# 5_Cooling_Control.net
KiCad netlist of a schematic drawn in Altium Designer
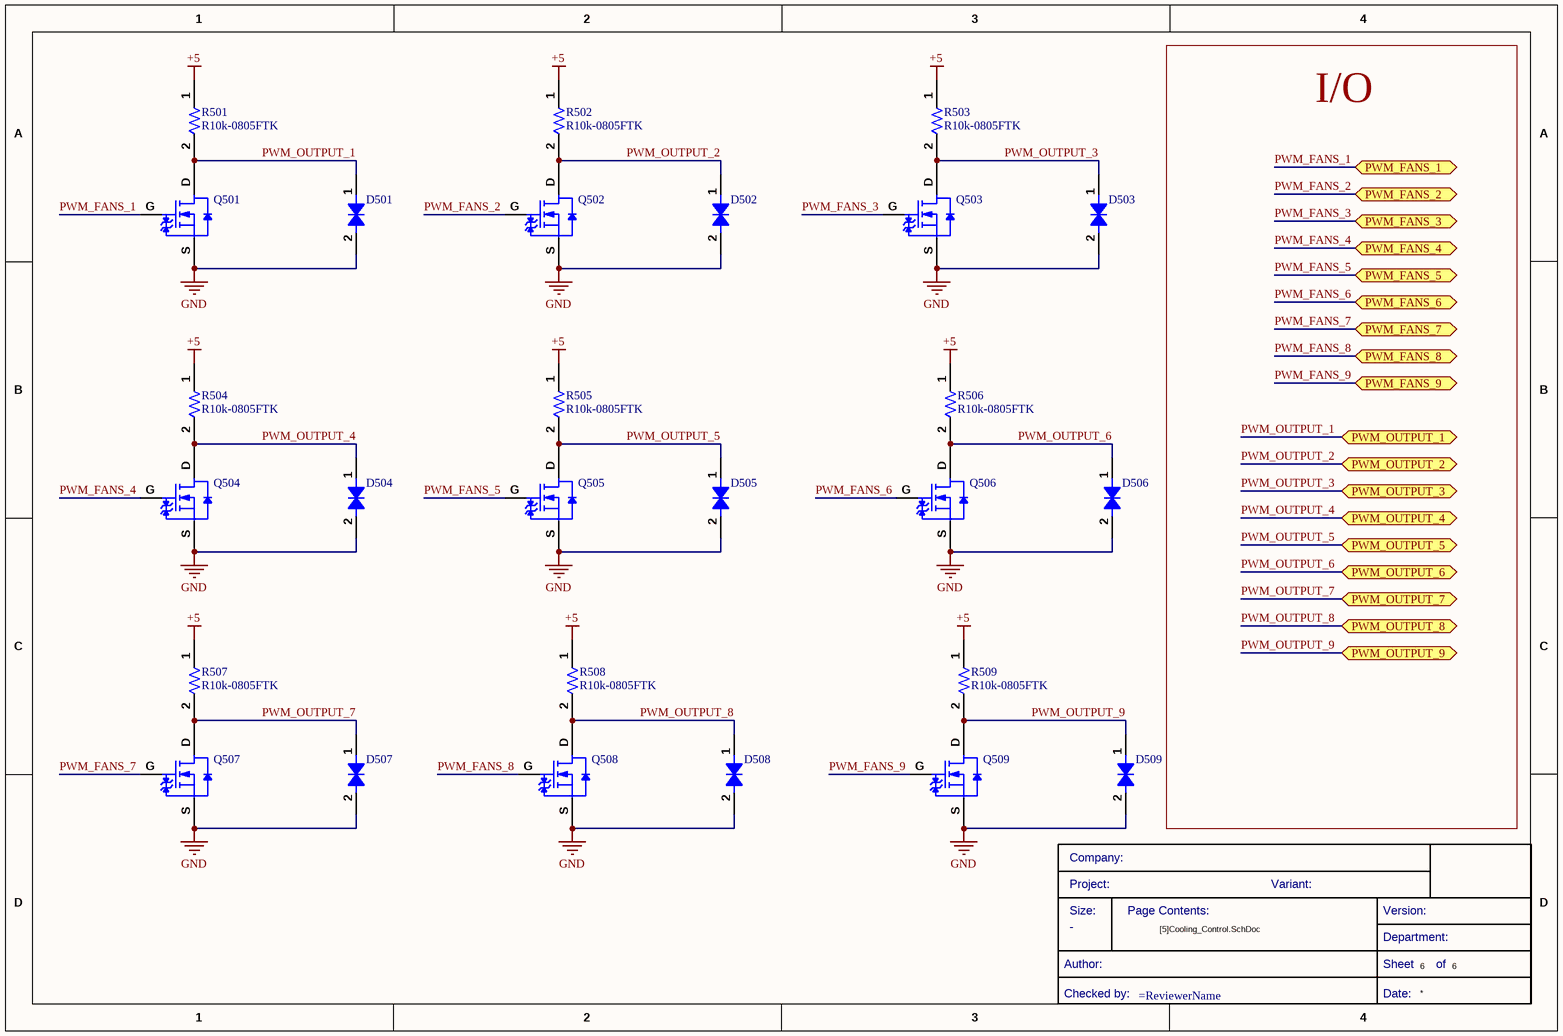
[diagram p0: [5]Cooling_Control.SchDoc]

(export (version "E")
  (design (tool "Eeschema 10.0.6"))
  (components
    (comp (ref "D501")
      (value "DTVS-13V-DO-214AC")
      (footprint "DTVS-DO-214AC")
      (description "Tvs Diode, 400W, 13V, Bidir, DO-214AC")
      (fields
        (field (name "MANUFACTURER PART NUMBER") "824501131")
        (field (name "MANUFACTURER") "Wurth Electronics")
        (field (name ".CREATOR") "DO")
      )
      (libsource (lib "EMEA- E-Tech Racing- I'Escola d'Enginyeria de Barcelona Est") (part "DTVS-BD-30k-SOD323"))
    )
    (comp (ref "D502")
      (value "DTVS-13V-DO-214AC")
      (footprint "DTVS-DO-214AC")
      (description "Tvs Diode, 400W, 13V, Bidir, DO-214AC")
      (fields
        (field (name "MANUFACTURER PART NUMBER") "824501131")
        (field (name "MANUFACTURER") "Wurth Electronics")
        (field (name ".CREATOR") "DO")
      )
      (libsource (lib "EMEA- E-Tech Racing- I'Escola d'Enginyeria de Barcelona Est") (part "DTVS-BD-30k-SOD323"))
    )
    (comp (ref "D503")
      (value "DTVS-13V-DO-214AC")
      (footprint "DTVS-DO-214AC")
      (description "Tvs Diode, 400W, 13V, Bidir, DO-214AC")
      (fields
        (field (name "MANUFACTURER PART NUMBER") "824501131")
        (field (name "MANUFACTURER") "Wurth Electronics")
        (field (name ".CREATOR") "DO")
      )
      (libsource (lib "EMEA- E-Tech Racing- I'Escola d'Enginyeria de Barcelona Est") (part "DTVS-BD-30k-SOD323"))
    )
    (comp (ref "D504")
      (value "DTVS-13V-DO-214AC")
      (footprint "DTVS-DO-214AC")
      (description "Tvs Diode, 400W, 13V, Bidir, DO-214AC")
      (fields
        (field (name "MANUFACTURER PART NUMBER") "824501131")
        (field (name "MANUFACTURER") "Wurth Electronics")
        (field (name ".CREATOR") "DO")
      )
      (libsource (lib "EMEA- E-Tech Racing- I'Escola d'Enginyeria de Barcelona Est") (part "DTVS-BD-30k-SOD323"))
    )
    (comp (ref "D505")
      (value "DTVS-13V-DO-214AC")
      (footprint "DTVS-DO-214AC")
      (description "Tvs Diode, 400W, 13V, Bidir, DO-214AC")
      (fields
        (field (name "MANUFACTURER PART NUMBER") "824501131")
        (field (name "MANUFACTURER") "Wurth Electronics")
        (field (name ".CREATOR") "DO")
      )
      (libsource (lib "EMEA- E-Tech Racing- I'Escola d'Enginyeria de Barcelona Est") (part "DTVS-BD-30k-SOD323"))
    )
    (comp (ref "D506")
      (value "DTVS-13V-DO-214AC")
      (footprint "DTVS-DO-214AC")
      (description "Tvs Diode, 400W, 13V, Bidir, DO-214AC")
      (fields
        (field (name "MANUFACTURER PART NUMBER") "824501131")
        (field (name "MANUFACTURER") "Wurth Electronics")
        (field (name ".CREATOR") "DO")
      )
      (libsource (lib "EMEA- E-Tech Racing- I'Escola d'Enginyeria de Barcelona Est") (part "DTVS-BD-30k-SOD323"))
    )
    (comp (ref "D507")
      (value "DTVS-13V-DO-214AC")
      (footprint "DTVS-DO-214AC")
      (description "Tvs Diode, 400W, 13V, Bidir, DO-214AC")
      (fields
        (field (name "MANUFACTURER PART NUMBER") "824501131")
        (field (name "MANUFACTURER") "Wurth Electronics")
        (field (name ".CREATOR") "DO")
      )
      (libsource (lib "EMEA- E-Tech Racing- I'Escola d'Enginyeria de Barcelona Est") (part "DTVS-BD-30k-SOD323"))
    )
    (comp (ref "D508")
      (value "DTVS-13V-DO-214AC")
      (footprint "DTVS-DO-214AC")
      (description "Tvs Diode, 400W, 13V, Bidir, DO-214AC")
      (fields
        (field (name "MANUFACTURER PART NUMBER") "824501131")
        (field (name "MANUFACTURER") "Wurth Electronics")
        (field (name ".CREATOR") "DO")
      )
      (libsource (lib "EMEA- E-Tech Racing- I'Escola d'Enginyeria de Barcelona Est") (part "DTVS-BD-30k-SOD323"))
    )
    (comp (ref "D509")
      (value "DTVS-13V-DO-214AC")
      (footprint "DTVS-DO-214AC")
      (description "Tvs Diode, 400W, 13V, Bidir, DO-214AC")
      (fields
        (field (name "MANUFACTURER PART NUMBER") "824501131")
        (field (name "MANUFACTURER") "Wurth Electronics")
        (field (name ".CREATOR") "DO")
      )
      (libsource (lib "EMEA- E-Tech Racing- I'Escola d'Enginyeria de Barcelona Est") (part "DTVS-BD-30k-SOD323"))
    )
    (comp (ref "Q501")
      (value "SQ2318CES-T1_GE3")
      (footprint "SOT95P245X110-3N")
      (description "Mosfet, N-channel, 40V, 7A, SOT-23 Rohs Compliant: Yes")
      (libsource (lib "EMEA- E-Tech Racing- I'Escola d'Enginyeria de Barcelona Est") (part "TRT-NCH-3/35-CPH"))
    )
    (comp (ref "Q502")
      (value "SQ2318CES-T1_GE3")
      (footprint "SOT95P245X110-3N")
      (description "Mosfet, N-channel, 40V, 7A, SOT-23 Rohs Compliant: Yes")
      (libsource (lib "EMEA- E-Tech Racing- I'Escola d'Enginyeria de Barcelona Est") (part "TRT-NCH-3/35-CPH"))
    )
    (comp (ref "Q503")
      (value "SQ2318CES-T1_GE3")
      (footprint "SOT95P245X110-3N")
      (description "Mosfet, N-channel, 40V, 7A, SOT-23 Rohs Compliant: Yes")
      (libsource (lib "EMEA- E-Tech Racing- I'Escola d'Enginyeria de Barcelona Est") (part "TRT-NCH-3/35-CPH"))
    )
    (comp (ref "Q504")
      (value "SQ2318CES-T1_GE3")
      (footprint "SOT95P245X110-3N")
      (description "Mosfet, N-channel, 40V, 7A, SOT-23 Rohs Compliant: Yes")
      (libsource (lib "EMEA- E-Tech Racing- I'Escola d'Enginyeria de Barcelona Est") (part "TRT-NCH-3/35-CPH"))
    )
    (comp (ref "Q505")
      (value "SQ2318CES-T1_GE3")
      (footprint "SOT95P245X110-3N")
      (description "Mosfet, N-channel, 40V, 7A, SOT-23 Rohs Compliant: Yes")
      (libsource (lib "EMEA- E-Tech Racing- I'Escola d'Enginyeria de Barcelona Est") (part "TRT-NCH-3/35-CPH"))
    )
    (comp (ref "Q506")
      (value "SQ2318CES-T1_GE3")
      (footprint "SOT95P245X110-3N")
      (description "Mosfet, N-channel, 40V, 7A, SOT-23 Rohs Compliant: Yes")
      (libsource (lib "EMEA- E-Tech Racing- I'Escola d'Enginyeria de Barcelona Est") (part "TRT-NCH-3/35-CPH"))
    )
    (comp (ref "Q507")
      (value "SQ2318CES-T1_GE3")
      (footprint "SOT95P245X110-3N")
      (description "Mosfet, N-channel, 40V, 7A, SOT-23 Rohs Compliant: Yes")
      (libsource (lib "EMEA- E-Tech Racing- I'Escola d'Enginyeria de Barcelona Est") (part "TRT-NCH-3/35-CPH"))
    )
    (comp (ref "Q508")
      (value "SQ2318CES-T1_GE3")
      (footprint "SOT95P245X110-3N")
      (description "Mosfet, N-channel, 40V, 7A, SOT-23 Rohs Compliant: Yes")
      (libsource (lib "EMEA- E-Tech Racing- I'Escola d'Enginyeria de Barcelona Est") (part "TRT-NCH-3/35-CPH"))
    )
    (comp (ref "Q509")
      (value "SQ2318CES-T1_GE3")
      (footprint "SOT95P245X110-3N")
      (description "Mosfet, N-channel, 40V, 7A, SOT-23 Rohs Compliant: Yes")
      (libsource (lib "EMEA- E-Tech Racing- I'Escola d'Enginyeria de Barcelona Est") (part "TRT-NCH-3/35-CPH"))
    )
    (comp (ref "R501")
      (value "R10k-0805FTK")
      (footprint "R0805FTK")
      (fields (field (name "TOLERANCE") "5%") (field (name ".CREATOR") "DR"))
      (libsource (lib "EMEA- E-Tech Racing- I'Escola d'Enginyeria de Barcelona Est") (part "R9.09K-1206FTK"))
    )
    (comp (ref "R502")
      (value "R10k-0805FTK")
      (footprint "R0805FTK")
      (fields (field (name "TOLERANCE") "5%") (field (name ".CREATOR") "DR"))
      (libsource (lib "EMEA- E-Tech Racing- I'Escola d'Enginyeria de Barcelona Est") (part "R9.09K-1206FTK"))
    )
    (comp (ref "R503")
      (value "R10k-0805FTK")
      (footprint "R0805FTK")
      (fields (field (name "TOLERANCE") "5%") (field (name ".CREATOR") "DR"))
      (libsource (lib "EMEA- E-Tech Racing- I'Escola d'Enginyeria de Barcelona Est") (part "R9.09K-1206FTK"))
    )
    (comp (ref "R504")
      (value "R10k-0805FTK")
      (footprint "R0805FTK")
      (fields (field (name "TOLERANCE") "5%") (field (name ".CREATOR") "DR"))
      (libsource (lib "EMEA- E-Tech Racing- I'Escola d'Enginyeria de Barcelona Est") (part "R9.09K-1206FTK"))
    )
    (comp (ref "R505")
      (value "R10k-0805FTK")
      (footprint "R0805FTK")
      (fields (field (name "TOLERANCE") "5%") (field (name ".CREATOR") "DR"))
      (libsource (lib "EMEA- E-Tech Racing- I'Escola d'Enginyeria de Barcelona Est") (part "R9.09K-1206FTK"))
    )
    (comp (ref "R506")
      (value "R10k-0805FTK")
      (footprint "R0805FTK")
      (fields (field (name "TOLERANCE") "5%") (field (name ".CREATOR") "DR"))
      (libsource (lib "EMEA- E-Tech Racing- I'Escola d'Enginyeria de Barcelona Est") (part "R9.09K-1206FTK"))
    )
    (comp (ref "R507")
      (value "R10k-0805FTK")
      (footprint "R0805FTK")
      (fields (field (name "TOLERANCE") "5%") (field (name ".CREATOR") "DR"))
      (libsource (lib "EMEA- E-Tech Racing- I'Escola d'Enginyeria de Barcelona Est") (part "R9.09K-1206FTK"))
    )
    (comp (ref "R508")
      (value "R10k-0805FTK")
      (footprint "R0805FTK")
      (fields (field (name "TOLERANCE") "5%") (field (name ".CREATOR") "DR"))
      (libsource (lib "EMEA- E-Tech Racing- I'Escola d'Enginyeria de Barcelona Est") (part "R9.09K-1206FTK"))
    )
    (comp (ref "R509")
      (value "R10k-0805FTK")
      (footprint "R0805FTK")
      (fields (field (name "TOLERANCE") "5%") (field (name ".CREATOR") "DR"))
      (libsource (lib "EMEA- E-Tech Racing- I'Escola d'Enginyeria de Barcelona Est") (part "R9.09K-1206FTK"))
    )
  )
  (nets
    (net (code "1") (name "+5") (class "Default")
      (node (ref "R501") (pin "1") (pinfunction "1_1") (pintype "passive"))
      (node (ref "R502") (pin "1") (pinfunction "1_1") (pintype "passive"))
      (node (ref "R503") (pin "1") (pinfunction "1_1") (pintype "passive"))
      (node (ref "R504") (pin "1") (pinfunction "1_1") (pintype "passive"))
      (node (ref "R505") (pin "1") (pinfunction "1_1") (pintype "passive"))
      (node (ref "R506") (pin "1") (pinfunction "1_1") (pintype "passive"))
      (node (ref "R507") (pin "1") (pinfunction "1_1") (pintype "passive"))
      (node (ref "R508") (pin "1") (pinfunction "1_1") (pintype "passive"))
      (node (ref "R509") (pin "1") (pinfunction "1_1") (pintype "passive"))
    )
    (net (code "2") (name "/PWM_FANS_1") (class "Default")
      (node (ref "Q501") (pin "G") (pinfunction "G_G") (pintype "passive"))
    )
    (net (code "3") (name "/PWM_FANS_2") (class "Default")
      (node (ref "Q502") (pin "G") (pinfunction "G_G") (pintype "passive"))
    )
    (net (code "4") (name "/PWM_FANS_3") (class "Default")
      (node (ref "Q503") (pin "G") (pinfunction "G_G") (pintype "passive"))
    )
    (net (code "5") (name "/PWM_FANS_4") (class "Default")
      (node (ref "Q504") (pin "G") (pinfunction "G_G") (pintype "passive"))
    )
    (net (code "6") (name "/PWM_FANS_5") (class "Default")
      (node (ref "Q505") (pin "G") (pinfunction "G_G") (pintype "passive"))
    )
    (net (code "7") (name "/PWM_FANS_6") (class "Default")
      (node (ref "Q506") (pin "G") (pinfunction "G_G") (pintype "passive"))
    )
    (net (code "8") (name "/PWM_FANS_7") (class "Default")
      (node (ref "Q507") (pin "G") (pinfunction "G_G") (pintype "passive"))
    )
    (net (code "9") (name "/PWM_FANS_8") (class "Default")
      (node (ref "Q508") (pin "G") (pinfunction "G_G") (pintype "passive"))
    )
    (net (code "10") (name "/PWM_FANS_9") (class "Default")
      (node (ref "Q509") (pin "G") (pinfunction "G_G") (pintype "passive"))
    )
    (net (code "11") (name "/PWM_OUTPUT_1") (class "Default")
      (node (ref "D501") (pin "1") (pinfunction "1_1") (pintype "passive"))
      (node (ref "Q501") (pin "D") (pinfunction "D_D") (pintype "passive"))
      (node (ref "R501") (pin "2") (pinfunction "2_2") (pintype "passive"))
    )
    (net (code "12") (name "/PWM_OUTPUT_2") (class "Default")
      (node (ref "D502") (pin "1") (pinfunction "1_1") (pintype "passive"))
      (node (ref "Q502") (pin "D") (pinfunction "D_D") (pintype "passive"))
      (node (ref "R502") (pin "2") (pinfunction "2_2") (pintype "passive"))
    )
    (net (code "13") (name "/PWM_OUTPUT_3") (class "Default")
      (node (ref "D503") (pin "1") (pinfunction "1_1") (pintype "passive"))
      (node (ref "Q503") (pin "D") (pinfunction "D_D") (pintype "passive"))
      (node (ref "R503") (pin "2") (pinfunction "2_2") (pintype "passive"))
    )
    (net (code "14") (name "/PWM_OUTPUT_4") (class "Default")
      (node (ref "D504") (pin "1") (pinfunction "1_1") (pintype "passive"))
      (node (ref "Q504") (pin "D") (pinfunction "D_D") (pintype "passive"))
      (node (ref "R504") (pin "2") (pinfunction "2_2") (pintype "passive"))
    )
    (net (code "15") (name "/PWM_OUTPUT_5") (class "Default")
      (node (ref "D505") (pin "1") (pinfunction "1_1") (pintype "passive"))
      (node (ref "Q505") (pin "D") (pinfunction "D_D") (pintype "passive"))
      (node (ref "R505") (pin "2") (pinfunction "2_2") (pintype "passive"))
    )
    (net (code "16") (name "/PWM_OUTPUT_6") (class "Default")
      (node (ref "D506") (pin "1") (pinfunction "1_1") (pintype "passive"))
      (node (ref "Q506") (pin "D") (pinfunction "D_D") (pintype "passive"))
      (node (ref "R506") (pin "2") (pinfunction "2_2") (pintype "passive"))
    )
    (net (code "17") (name "/PWM_OUTPUT_7") (class "Default")
      (node (ref "D507") (pin "1") (pinfunction "1_1") (pintype "passive"))
      (node (ref "Q507") (pin "D") (pinfunction "D_D") (pintype "passive"))
      (node (ref "R507") (pin "2") (pinfunction "2_2") (pintype "passive"))
    )
    (net (code "18") (name "/PWM_OUTPUT_8") (class "Default")
      (node (ref "D508") (pin "1") (pinfunction "1_1") (pintype "passive"))
      (node (ref "Q508") (pin "D") (pinfunction "D_D") (pintype "passive"))
      (node (ref "R508") (pin "2") (pinfunction "2_2") (pintype "passive"))
    )
    (net (code "19") (name "/PWM_OUTPUT_9") (class "Default")
      (node (ref "D509") (pin "1") (pinfunction "1_1") (pintype "passive"))
      (node (ref "Q509") (pin "D") (pinfunction "D_D") (pintype "passive"))
      (node (ref "R509") (pin "2") (pinfunction "2_2") (pintype "passive"))
    )
    (net (code "20") (name "GND") (class "Default")
      (node (ref "D501") (pin "2") (pinfunction "2_2") (pintype "passive"))
      (node (ref "D502") (pin "2") (pinfunction "2_2") (pintype "passive"))
      (node (ref "D503") (pin "2") (pinfunction "2_2") (pintype "passive"))
      (node (ref "D504") (pin "2") (pinfunction "2_2") (pintype "passive"))
      (node (ref "D505") (pin "2") (pinfunction "2_2") (pintype "passive"))
      (node (ref "D506") (pin "2") (pinfunction "2_2") (pintype "passive"))
      (node (ref "D507") (pin "2") (pinfunction "2_2") (pintype "passive"))
      (node (ref "D508") (pin "2") (pinfunction "2_2") (pintype "passive"))
      (node (ref "D509") (pin "2") (pinfunction "2_2") (pintype "passive"))
      (node (ref "Q501") (pin "S") (pinfunction "S_S") (pintype "passive"))
      (node (ref "Q502") (pin "S") (pinfunction "S_S") (pintype "passive"))
      (node (ref "Q503") (pin "S") (pinfunction "S_S") (pintype "passive"))
      (node (ref "Q504") (pin "S") (pinfunction "S_S") (pintype "passive"))
      (node (ref "Q505") (pin "S") (pinfunction "S_S") (pintype "passive"))
      (node (ref "Q506") (pin "S") (pinfunction "S_S") (pintype "passive"))
      (node (ref "Q507") (pin "S") (pinfunction "S_S") (pintype "passive"))
      (node (ref "Q508") (pin "S") (pinfunction "S_S") (pintype "passive"))
      (node (ref "Q509") (pin "S") (pinfunction "S_S") (pintype "passive"))
    )
  )
)
